# raspi-gsm-relais.net
KiCad netlist of a schematic drawn in EAGLE
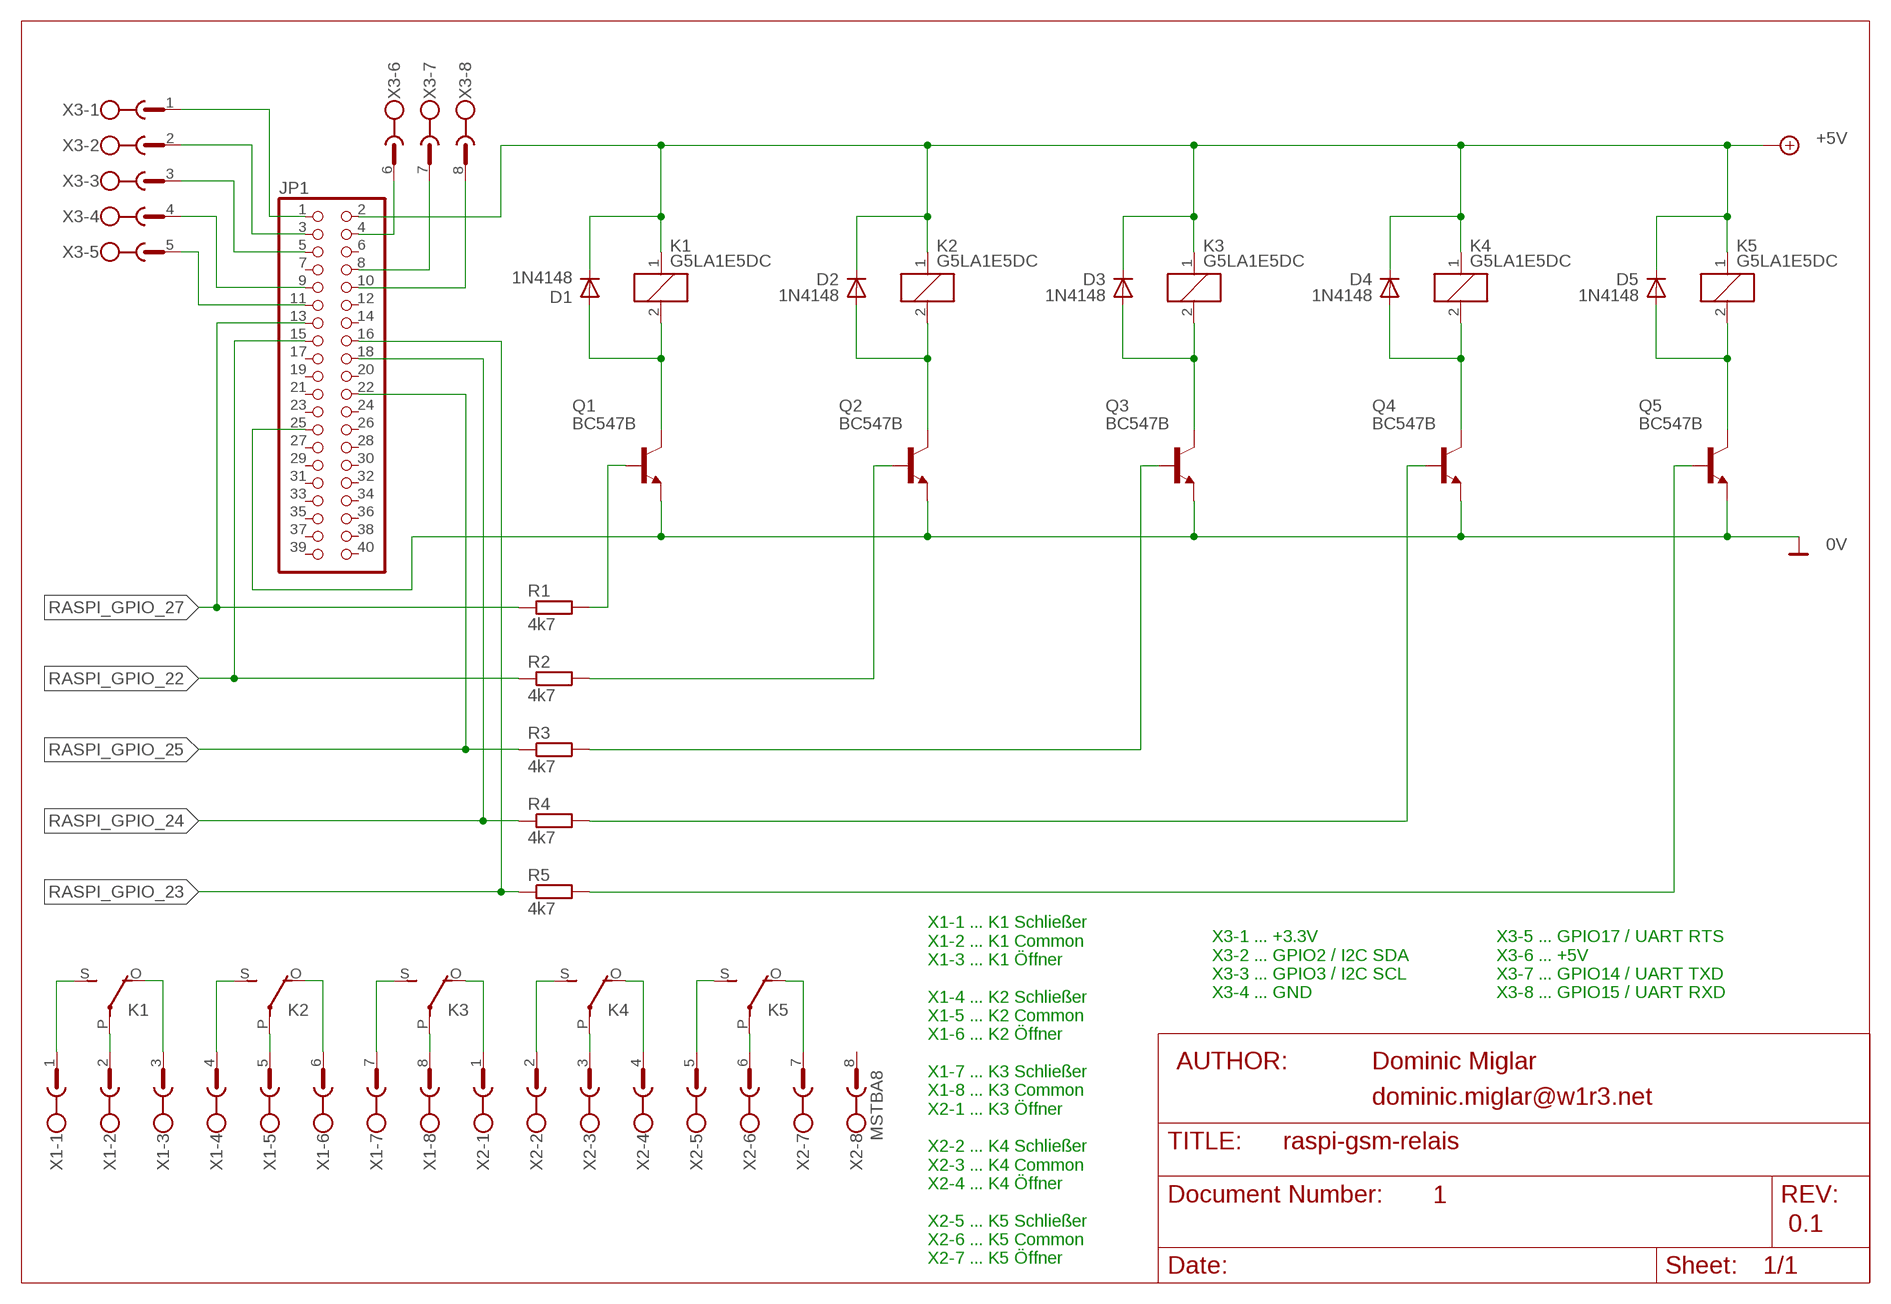
[diagram p0: schematic, sheet 1]

(export (version "E")
  (design (tool "Eeschema 10.0.6"))
  (components
    (comp (ref "D1")
      (value "1N4148")
      (footprint "eagle-import:DO35-10")
      (libsource (lib "eagle-import") (part "1N4148DO35-10"))
    )
    (comp (ref "D2")
      (value "1N4148")
      (footprint "eagle-import:DO35-10")
      (libsource (lib "eagle-import") (part "1N4148DO35-10"))
    )
    (comp (ref "D3")
      (value "1N4148")
      (footprint "eagle-import:DO35-10")
      (libsource (lib "eagle-import") (part "1N4148DO35-10"))
    )
    (comp (ref "D4")
      (value "1N4148")
      (footprint "eagle-import:DO35-10")
      (libsource (lib "eagle-import") (part "1N4148DO35-10"))
    )
    (comp (ref "D5")
      (value "1N4148")
      (footprint "eagle-import:DO35-10")
      (libsource (lib "eagle-import") (part "1N4148DO35-10"))
    )
    (comp (ref "JP1")
      (value "PINHD-2X20")
      (footprint "eagle-import:2X20")
      (libsource (lib "eagle-import") (part "PINHD-2X20"))
    )
    (comp (ref "K1")
      (value "G5LA1E5DC")
      (footprint "eagle-import:G5LE")
      (libsource (lib "eagle-import") (part "G5L"))
    )
    (comp (ref "K2")
      (value "G5LA1E5DC")
      (footprint "eagle-import:G5LE")
      (libsource (lib "eagle-import") (part "G5L"))
    )
    (comp (ref "K3")
      (value "G5LA1E5DC")
      (footprint "eagle-import:G5LE")
      (libsource (lib "eagle-import") (part "G5L"))
    )
    (comp (ref "K4")
      (value "G5LA1E5DC")
      (footprint "eagle-import:G5LE")
      (libsource (lib "eagle-import") (part "G5L"))
    )
    (comp (ref "K5")
      (value "G5LA1E5DC")
      (footprint "eagle-import:G5LE")
      (libsource (lib "eagle-import") (part "G5L"))
    )
    (comp (ref "Q1")
      (value "BC547B")
      (footprint "eagle-import:TO92")
      (libsource (lib "eagle-import") (part "BC547B"))
    )
    (comp (ref "Q2")
      (value "BC547B")
      (footprint "eagle-import:TO92")
      (libsource (lib "eagle-import") (part "BC547B"))
    )
    (comp (ref "Q3")
      (value "BC547B")
      (footprint "eagle-import:TO92")
      (libsource (lib "eagle-import") (part "BC547B"))
    )
    (comp (ref "Q4")
      (value "BC547B")
      (footprint "eagle-import:TO92")
      (libsource (lib "eagle-import") (part "BC547B"))
    )
    (comp (ref "Q5")
      (value "BC547B")
      (footprint "eagle-import:TO92")
      (libsource (lib "eagle-import") (part "BC547B"))
    )
    (comp (ref "R1")
      (value "4k7")
      (footprint "eagle-import:0207_10")
      (libsource (lib "eagle-import") (part "R-EU_0207/10"))
    )
    (comp (ref "R2")
      (value "4k7")
      (footprint "eagle-import:0207_10")
      (libsource (lib "eagle-import") (part "R-EU_0207/10"))
    )
    (comp (ref "R3")
      (value "4k7")
      (footprint "eagle-import:0207_10")
      (libsource (lib "eagle-import") (part "R-EU_0207/10"))
    )
    (comp (ref "R4")
      (value "4k7")
      (footprint "eagle-import:0207_10")
      (libsource (lib "eagle-import") (part "R-EU_0207/10"))
    )
    (comp (ref "R5")
      (value "4k7")
      (footprint "eagle-import:0207_10")
      (libsource (lib "eagle-import") (part "R-EU_0207/10"))
    )
    (comp (ref "X1")
      (value "MSTBA8")
      (footprint "eagle-import:MSTBA8")
      (fields (field (name "MF") "FARNELL") (field (name "MPN") "1757307"))
      (libsource (lib "eagle-import") (part "MSTBA8"))
    )
    (comp (ref "X2")
      (value "MSTBA8")
      (footprint "eagle-import:MSTBA8")
      (fields (field (name "MF") "FARNELL") (field (name "MPN") "1757307"))
      (libsource (lib "eagle-import") (part "MSTBA8"))
    )
    (comp (ref "X3")
      (value "MSTBA8")
      (footprint "eagle-import:MSTBA8")
      (fields (field (name "MF") "FARNELL") (field (name "MPN") "1757307"))
      (libsource (lib "eagle-import") (part "MSTBA8"))
    )
  )
  (nets
    (net (code "1") (name "+5V") (class "Default")
      (node (ref "D1") (pin "C") (pinfunction "C_C") (pintype "passive"))
      (node (ref "D2") (pin "C") (pinfunction "C_C") (pintype "passive"))
      (node (ref "D3") (pin "C") (pinfunction "C_C") (pintype "passive"))
      (node (ref "D4") (pin "C") (pinfunction "C_C") (pintype "passive"))
      (node (ref "D5") (pin "C") (pinfunction "C_C") (pintype "passive"))
      (node (ref "JP1") (pin "2") (pinfunction "2_2") (pintype "passive"))
      (node (ref "K1") (pin "1") (pinfunction "1_1") (pintype "passive"))
      (node (ref "K2") (pin "1") (pinfunction "1_1") (pintype "passive"))
      (node (ref "K3") (pin "1") (pinfunction "1_1") (pintype "passive"))
      (node (ref "K4") (pin "1") (pinfunction "1_1") (pintype "passive"))
      (node (ref "K5") (pin "1") (pinfunction "1_1") (pintype "passive"))
    )
    (net (code "2") (name "0V") (class "Default")
      (node (ref "JP1") (pin "25") (pinfunction "25_25") (pintype "passive"))
      (node (ref "Q1") (pin "1") (pinfunction "E_1") (pintype "passive"))
      (node (ref "Q2") (pin "1") (pinfunction "E_1") (pintype "passive"))
      (node (ref "Q3") (pin "1") (pinfunction "E_1") (pintype "passive"))
      (node (ref "Q4") (pin "1") (pinfunction "E_1") (pintype "passive"))
      (node (ref "Q5") (pin "1") (pinfunction "E_1") (pintype "passive"))
    )
    (net (code "3") (name "Net-(JP1-Pad1)") (class "Default")
      (node (ref "JP1") (pin "1") (pinfunction "1_1") (pintype "passive"))
      (node (ref "X3") (pin "1") (pinfunction "1_1") (pintype "passive"))
    )
    (net (code "4") (name "Net-(K1-PadS)") (class "Default")
      (node (ref "K1") (pin "S") (pinfunction "S_S") (pintype "passive"))
      (node (ref "X1") (pin "1") (pinfunction "1_1") (pintype "passive"))
    )
    (net (code "5") (name "Net-(K3-PadO)") (class "Default")
      (node (ref "K3") (pin "O") (pinfunction "O_O") (pintype "passive"))
      (node (ref "X2") (pin "1") (pinfunction "1_1") (pintype "passive"))
    )
    (net (code "6") (name "Net-(Q1-B)") (class "Default")
      (node (ref "Q1") (pin "2") (pinfunction "B_2") (pintype "passive"))
      (node (ref "R1") (pin "2") (pinfunction "2_2") (pintype "passive"))
    )
    (net (code "7") (name "Net-(Q1-C)") (class "Default")
      (node (ref "D1") (pin "A") (pinfunction "A_A") (pintype "passive"))
      (node (ref "K1") (pin "2") (pinfunction "2_2") (pintype "passive"))
      (node (ref "Q1") (pin "3") (pinfunction "C_3") (pintype "passive"))
    )
    (net (code "8") (name "Net-(Q2-B)") (class "Default")
      (node (ref "Q2") (pin "2") (pinfunction "B_2") (pintype "passive"))
      (node (ref "R2") (pin "2") (pinfunction "2_2") (pintype "passive"))
    )
    (net (code "9") (name "Net-(Q2-C)") (class "Default")
      (node (ref "D2") (pin "A") (pinfunction "A_A") (pintype "passive"))
      (node (ref "K2") (pin "2") (pinfunction "2_2") (pintype "passive"))
      (node (ref "Q2") (pin "3") (pinfunction "C_3") (pintype "passive"))
    )
    (net (code "10") (name "Net-(Q3-B)") (class "Default")
      (node (ref "Q3") (pin "2") (pinfunction "B_2") (pintype "passive"))
      (node (ref "R3") (pin "2") (pinfunction "2_2") (pintype "passive"))
    )
    (net (code "11") (name "Net-(Q3-C)") (class "Default")
      (node (ref "D3") (pin "A") (pinfunction "A_A") (pintype "passive"))
      (node (ref "K3") (pin "2") (pinfunction "2_2") (pintype "passive"))
      (node (ref "Q3") (pin "3") (pinfunction "C_3") (pintype "passive"))
    )
    (net (code "12") (name "Net-(Q4-B)") (class "Default")
      (node (ref "Q4") (pin "2") (pinfunction "B_2") (pintype "passive"))
      (node (ref "R4") (pin "2") (pinfunction "2_2") (pintype "passive"))
    )
    (net (code "13") (name "Net-(Q4-C)") (class "Default")
      (node (ref "D4") (pin "A") (pinfunction "A_A") (pintype "passive"))
      (node (ref "K4") (pin "2") (pinfunction "2_2") (pintype "passive"))
      (node (ref "Q4") (pin "3") (pinfunction "C_3") (pintype "passive"))
    )
    (net (code "14") (name "Net-(Q5-B)") (class "Default")
      (node (ref "Q5") (pin "2") (pinfunction "B_2") (pintype "passive"))
      (node (ref "R5") (pin "2") (pinfunction "2_2") (pintype "passive"))
    )
    (net (code "15") (name "Net-(Q5-C)") (class "Default")
      (node (ref "D5") (pin "A") (pinfunction "A_A") (pintype "passive"))
      (node (ref "K5") (pin "2") (pinfunction "2_2") (pintype "passive"))
      (node (ref "Q5") (pin "3") (pinfunction "C_3") (pintype "passive"))
    )
    (net (code "16") (name "Net-(X1B-1)") (class "Default")
      (node (ref "K1") (pin "P") (pinfunction "P_P") (pintype "passive"))
      (node (ref "X1") (pin "2") (pinfunction "1_2") (pintype "passive"))
    )
    (net (code "17") (name "Net-(X1C-1)") (class "Default")
      (node (ref "K1") (pin "O") (pinfunction "O_O") (pintype "passive"))
      (node (ref "X1") (pin "3") (pinfunction "1_3") (pintype "passive"))
    )
    (net (code "18") (name "Net-(X1D-1)") (class "Default")
      (node (ref "K2") (pin "S") (pinfunction "S_S") (pintype "passive"))
      (node (ref "X1") (pin "4") (pinfunction "1_4") (pintype "passive"))
    )
    (net (code "19") (name "Net-(X1E-1)") (class "Default")
      (node (ref "K2") (pin "P") (pinfunction "P_P") (pintype "passive"))
      (node (ref "X1") (pin "5") (pinfunction "1_5") (pintype "passive"))
    )
    (net (code "20") (name "Net-(X1F-1)") (class "Default")
      (node (ref "K2") (pin "O") (pinfunction "O_O") (pintype "passive"))
      (node (ref "X1") (pin "6") (pinfunction "1_6") (pintype "passive"))
    )
    (net (code "21") (name "Net-(X1G-1)") (class "Default")
      (node (ref "K3") (pin "S") (pinfunction "S_S") (pintype "passive"))
      (node (ref "X1") (pin "7") (pinfunction "1_7") (pintype "passive"))
    )
    (net (code "22") (name "Net-(X1H-1)") (class "Default")
      (node (ref "K3") (pin "P") (pinfunction "P_P") (pintype "passive"))
      (node (ref "X1") (pin "8") (pinfunction "1_8") (pintype "passive"))
    )
    (net (code "23") (name "Net-(X2B-1)") (class "Default")
      (node (ref "K4") (pin "S") (pinfunction "S_S") (pintype "passive"))
      (node (ref "X2") (pin "2") (pinfunction "1_2") (pintype "passive"))
    )
    (net (code "24") (name "Net-(X2C-1)") (class "Default")
      (node (ref "K4") (pin "P") (pinfunction "P_P") (pintype "passive"))
      (node (ref "X2") (pin "3") (pinfunction "1_3") (pintype "passive"))
    )
    (net (code "25") (name "Net-(X2D-1)") (class "Default")
      (node (ref "K4") (pin "O") (pinfunction "O_O") (pintype "passive"))
      (node (ref "X2") (pin "4") (pinfunction "1_4") (pintype "passive"))
    )
    (net (code "26") (name "Net-(X2E-1)") (class "Default")
      (node (ref "K5") (pin "S") (pinfunction "S_S") (pintype "passive"))
      (node (ref "X2") (pin "5") (pinfunction "1_5") (pintype "passive"))
    )
    (net (code "27") (name "Net-(X2F-1)") (class "Default")
      (node (ref "K5") (pin "P") (pinfunction "P_P") (pintype "passive"))
      (node (ref "X2") (pin "6") (pinfunction "1_6") (pintype "passive"))
    )
    (net (code "28") (name "Net-(X2G-1)") (class "Default")
      (node (ref "K5") (pin "O") (pinfunction "O_O") (pintype "passive"))
      (node (ref "X2") (pin "7") (pinfunction "1_7") (pintype "passive"))
    )
    (net (code "29") (name "Net-(X3B-1)") (class "Default")
      (node (ref "JP1") (pin "3") (pinfunction "3_3") (pintype "passive"))
      (node (ref "X3") (pin "2") (pinfunction "1_2") (pintype "passive"))
    )
    (net (code "30") (name "Net-(X3C-1)") (class "Default")
      (node (ref "JP1") (pin "5") (pinfunction "5_5") (pintype "passive"))
      (node (ref "X3") (pin "3") (pinfunction "1_3") (pintype "passive"))
    )
    (net (code "31") (name "Net-(X3D-1)") (class "Default")
      (node (ref "JP1") (pin "9") (pinfunction "9_9") (pintype "passive"))
      (node (ref "X3") (pin "4") (pinfunction "1_4") (pintype "passive"))
    )
    (net (code "32") (name "Net-(X3E-1)") (class "Default")
      (node (ref "JP1") (pin "11") (pinfunction "11_11") (pintype "passive"))
      (node (ref "X3") (pin "5") (pinfunction "1_5") (pintype "passive"))
    )
    (net (code "33") (name "Net-(X3F-1)") (class "Default")
      (node (ref "JP1") (pin "4") (pinfunction "4_4") (pintype "passive"))
      (node (ref "X3") (pin "6") (pinfunction "1_6") (pintype "passive"))
    )
    (net (code "34") (name "Net-(X3G-1)") (class "Default")
      (node (ref "JP1") (pin "8") (pinfunction "8_8") (pintype "passive"))
      (node (ref "X3") (pin "7") (pinfunction "1_7") (pintype "passive"))
    )
    (net (code "35") (name "Net-(X3H-1)") (class "Default")
      (node (ref "JP1") (pin "10") (pinfunction "10_10") (pintype "passive"))
      (node (ref "X3") (pin "8") (pinfunction "1_8") (pintype "passive"))
    )
    (net (code "36") (name "RASPI_GPIO_22") (class "Default")
      (node (ref "JP1") (pin "15") (pinfunction "15_15") (pintype "passive"))
      (node (ref "R2") (pin "1") (pinfunction "1_1") (pintype "passive"))
    )
    (net (code "37") (name "RASPI_GPIO_23") (class "Default")
      (node (ref "JP1") (pin "16") (pinfunction "16_16") (pintype "passive"))
      (node (ref "R5") (pin "1") (pinfunction "1_1") (pintype "passive"))
    )
    (net (code "38") (name "RASPI_GPIO_24") (class "Default")
      (node (ref "JP1") (pin "18") (pinfunction "18_18") (pintype "passive"))
      (node (ref "R4") (pin "1") (pinfunction "1_1") (pintype "passive"))
    )
    (net (code "39") (name "RASPI_GPIO_25") (class "Default")
      (node (ref "JP1") (pin "22") (pinfunction "22_22") (pintype "passive"))
      (node (ref "R3") (pin "1") (pinfunction "1_1") (pintype "passive"))
    )
    (net (code "40") (name "RASPI_GPIO_27") (class "Default")
      (node (ref "JP1") (pin "13") (pinfunction "13_13") (pintype "passive"))
      (node (ref "R1") (pin "1") (pinfunction "1_1") (pintype "passive"))
    )
    (net (code "41") (name "unconnected-(JP1-Pad6)") (class "Default")
      (node (ref "JP1") (pin "6") (pinfunction "6_6") (pintype "passive"))
    )
    (net (code "42") (name "unconnected-(JP1-Pad7)") (class "Default")
      (node (ref "JP1") (pin "7") (pinfunction "7_7") (pintype "passive"))
    )
    (net (code "43") (name "unconnected-(JP1-Pad12)") (class "Default")
      (node (ref "JP1") (pin "12") (pinfunction "12_12") (pintype "passive"))
    )
    (net (code "44") (name "unconnected-(JP1-Pad14)") (class "Default")
      (node (ref "JP1") (pin "14") (pinfunction "14_14") (pintype "passive"))
    )
    (net (code "45") (name "unconnected-(JP1-Pad17)") (class "Default")
      (node (ref "JP1") (pin "17") (pinfunction "17_17") (pintype "passive"))
    )
    (net (code "46") (name "unconnected-(JP1-Pad19)") (class "Default")
      (node (ref "JP1") (pin "19") (pinfunction "19_19") (pintype "passive"))
    )
    (net (code "47") (name "unconnected-(JP1-Pad20)") (class "Default")
      (node (ref "JP1") (pin "20") (pinfunction "20_20") (pintype "passive"))
    )
    (net (code "48") (name "unconnected-(JP1-Pad21)") (class "Default")
      (node (ref "JP1") (pin "21") (pinfunction "21_21") (pintype "passive"))
    )
    (net (code "49") (name "unconnected-(JP1-Pad23)") (class "Default")
      (node (ref "JP1") (pin "23") (pinfunction "23_23") (pintype "passive"))
    )
    (net (code "50") (name "unconnected-(JP1-Pad24)") (class "Default")
      (node (ref "JP1") (pin "24") (pinfunction "24_24") (pintype "passive"))
    )
    (net (code "51") (name "unconnected-(JP1-Pad26)") (class "Default")
      (node (ref "JP1") (pin "26") (pinfunction "26_26") (pintype "passive"))
    )
    (net (code "52") (name "unconnected-(JP1-Pad27)") (class "Default")
      (node (ref "JP1") (pin "27") (pinfunction "27_27") (pintype "passive"))
    )
    (net (code "53") (name "unconnected-(JP1-Pad28)") (class "Default")
      (node (ref "JP1") (pin "28") (pinfunction "28_28") (pintype "passive"))
    )
    (net (code "54") (name "unconnected-(JP1-Pad29)") (class "Default")
      (node (ref "JP1") (pin "29") (pinfunction "29_29") (pintype "passive"))
    )
    (net (code "55") (name "unconnected-(JP1-Pad30)") (class "Default")
      (node (ref "JP1") (pin "30") (pinfunction "30_30") (pintype "passive"))
    )
    (net (code "56") (name "unconnected-(JP1-Pad31)") (class "Default")
      (node (ref "JP1") (pin "31") (pinfunction "31_31") (pintype "passive"))
    )
    (net (code "57") (name "unconnected-(JP1-Pad32)") (class "Default")
      (node (ref "JP1") (pin "32") (pinfunction "32_32") (pintype "passive"))
    )
    (net (code "58") (name "unconnected-(JP1-Pad33)") (class "Default")
      (node (ref "JP1") (pin "33") (pinfunction "33_33") (pintype "passive"))
    )
    (net (code "59") (name "unconnected-(JP1-Pad34)") (class "Default")
      (node (ref "JP1") (pin "34") (pinfunction "34_34") (pintype "passive"))
    )
    (net (code "60") (name "unconnected-(JP1-Pad35)") (class "Default")
      (node (ref "JP1") (pin "35") (pinfunction "35_35") (pintype "passive"))
    )
    (net (code "61") (name "unconnected-(JP1-Pad36)") (class "Default")
      (node (ref "JP1") (pin "36") (pinfunction "36_36") (pintype "passive"))
    )
    (net (code "62") (name "unconnected-(JP1-Pad37)") (class "Default")
      (node (ref "JP1") (pin "37") (pinfunction "37_37") (pintype "passive"))
    )
    (net (code "63") (name "unconnected-(JP1-Pad38)") (class "Default")
      (node (ref "JP1") (pin "38") (pinfunction "38_38") (pintype "passive"))
    )
    (net (code "64") (name "unconnected-(JP1-Pad39)") (class "Default")
      (node (ref "JP1") (pin "39") (pinfunction "39_39") (pintype "passive"))
    )
    (net (code "65") (name "unconnected-(JP1-Pad40)") (class "Default")
      (node (ref "JP1") (pin "40") (pinfunction "40_40") (pintype "passive"))
    )
    (net (code "66") (name "unconnected-(X2H-1-Pad8)") (class "Default")
      (node (ref "X2") (pin "8") (pinfunction "1_8") (pintype "passive"))
    )
  )
)
